# mk312lite_V3.net
KiCad netlist of a schematic drawn in EAGLE
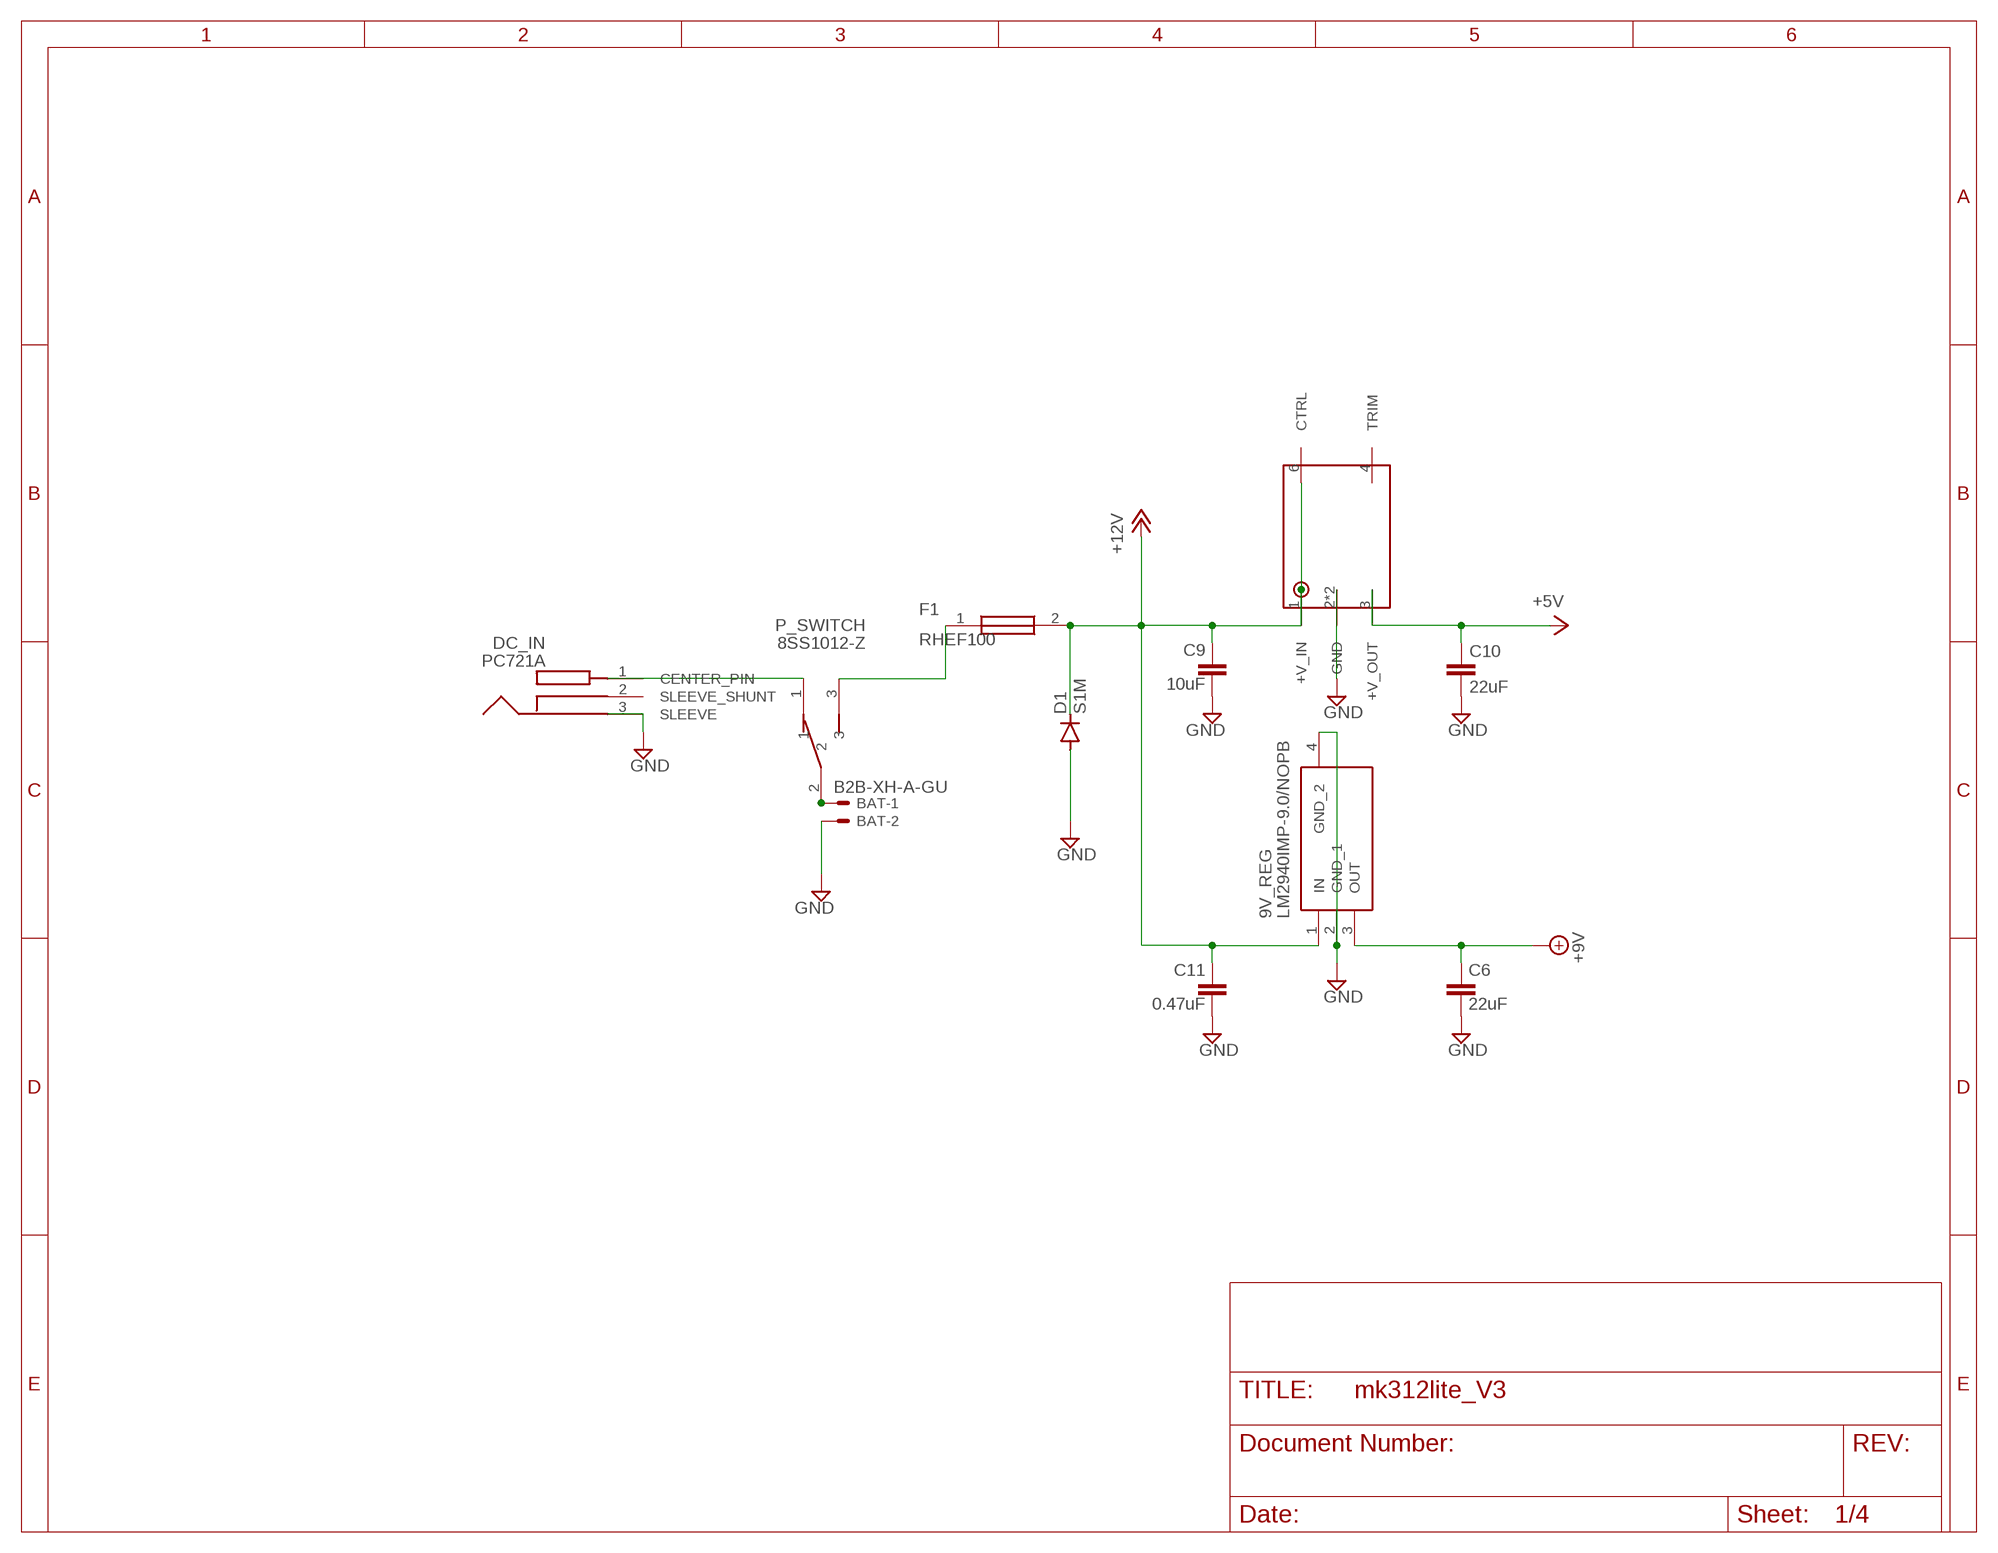
[diagram p0: schematic, sheet 1]
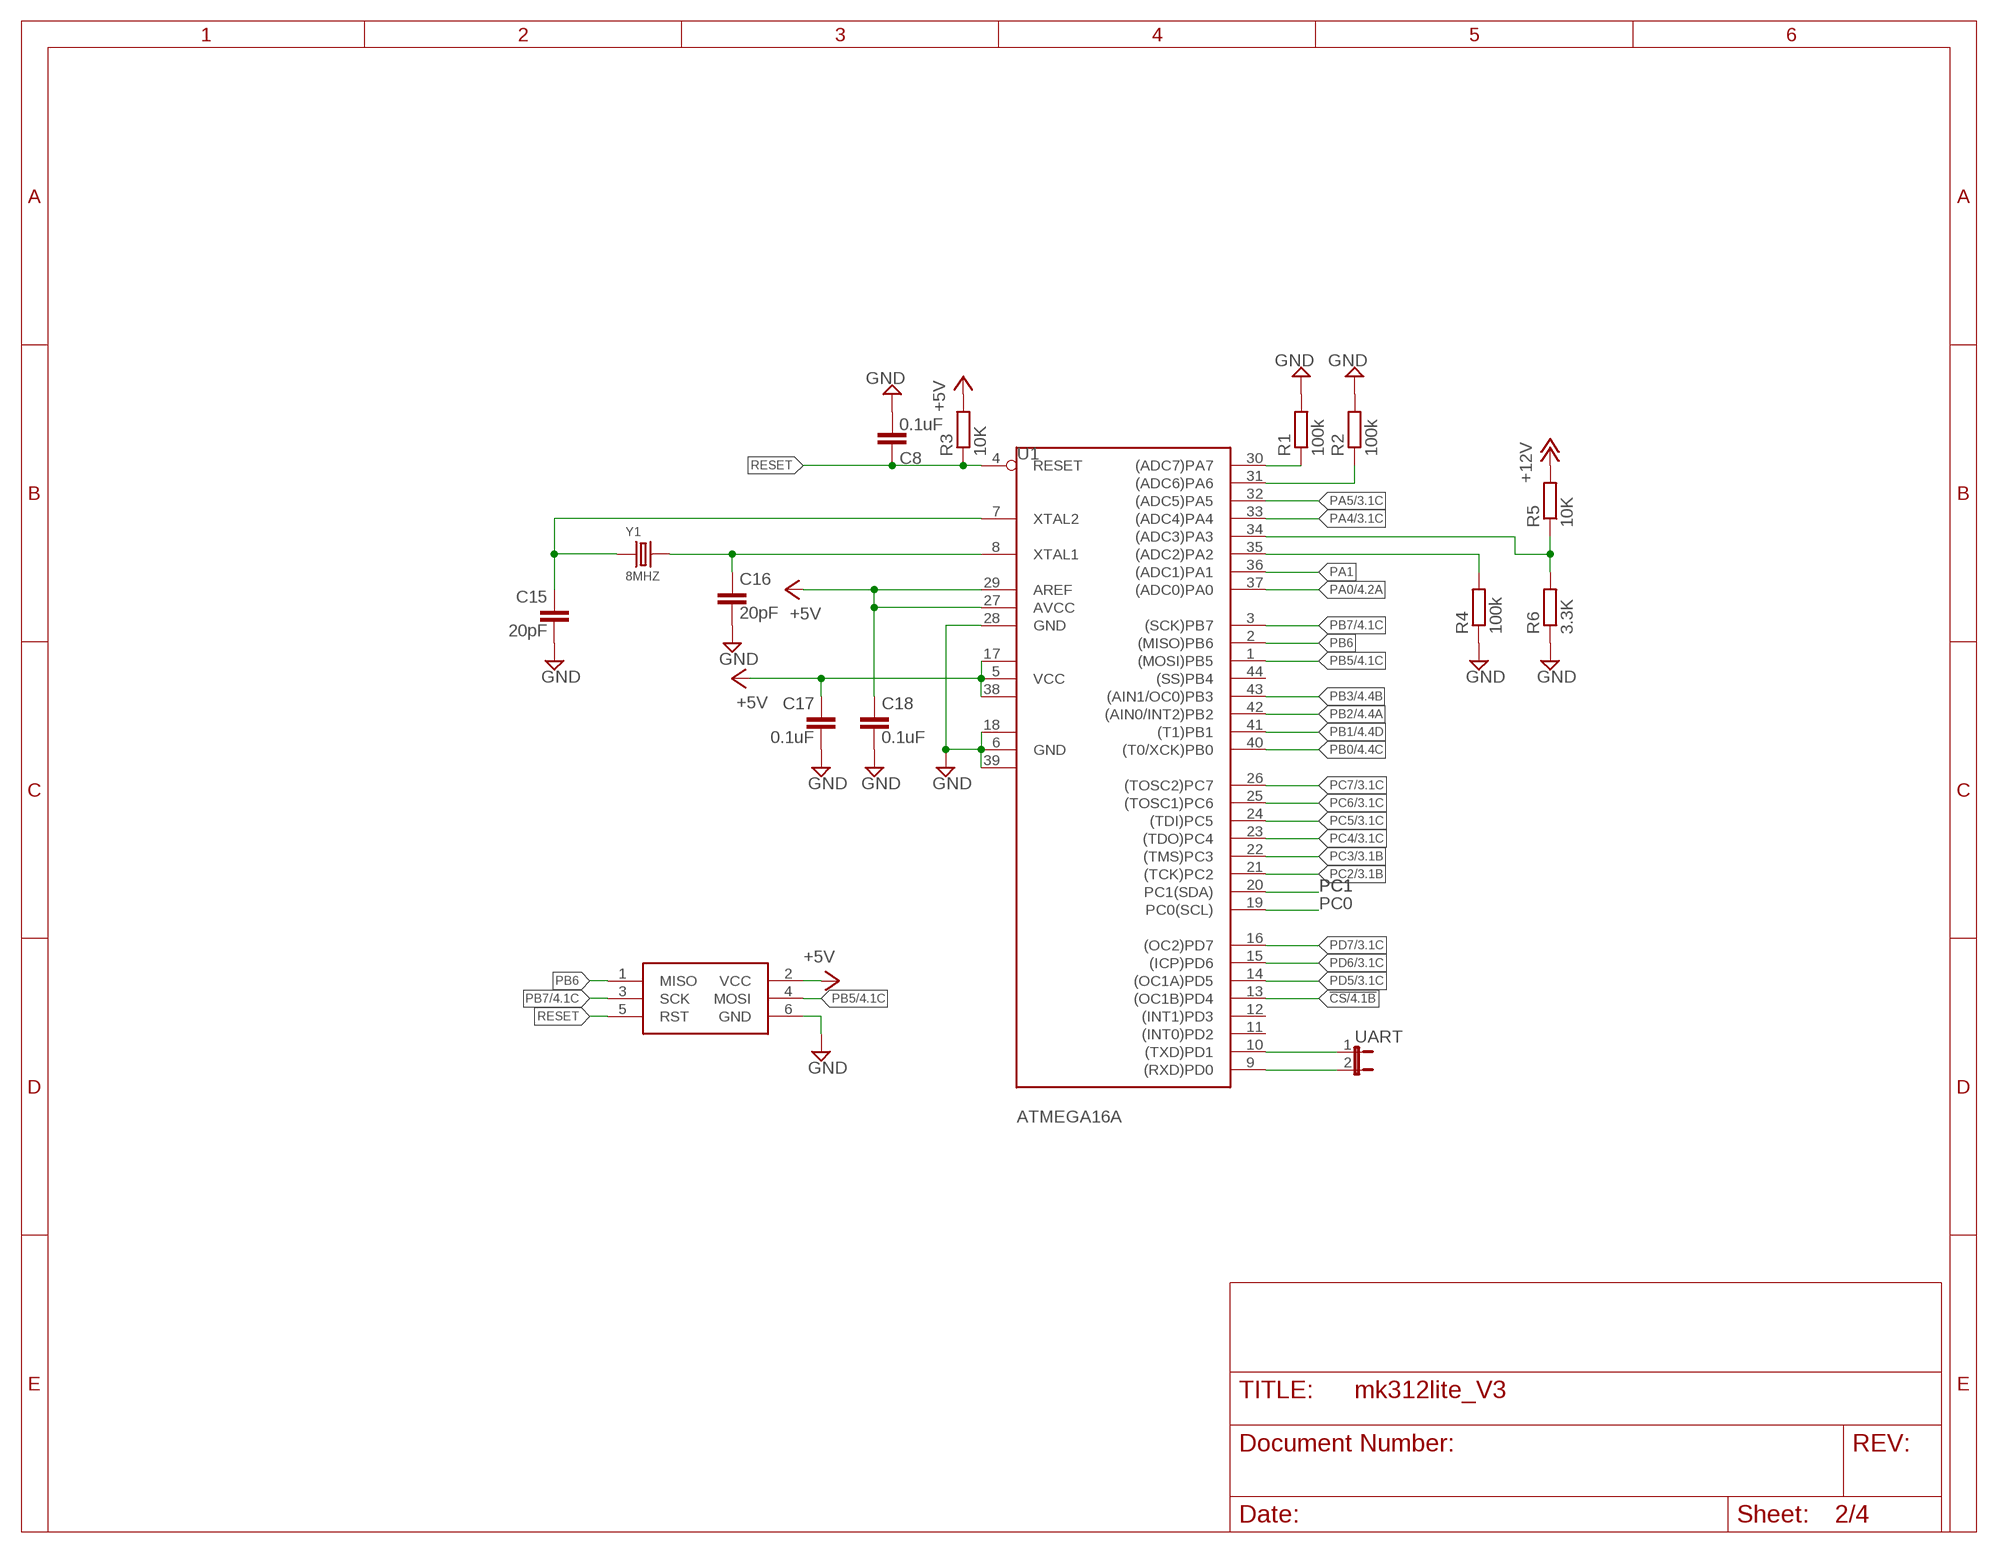
[diagram p1: schematic, sheet 2]
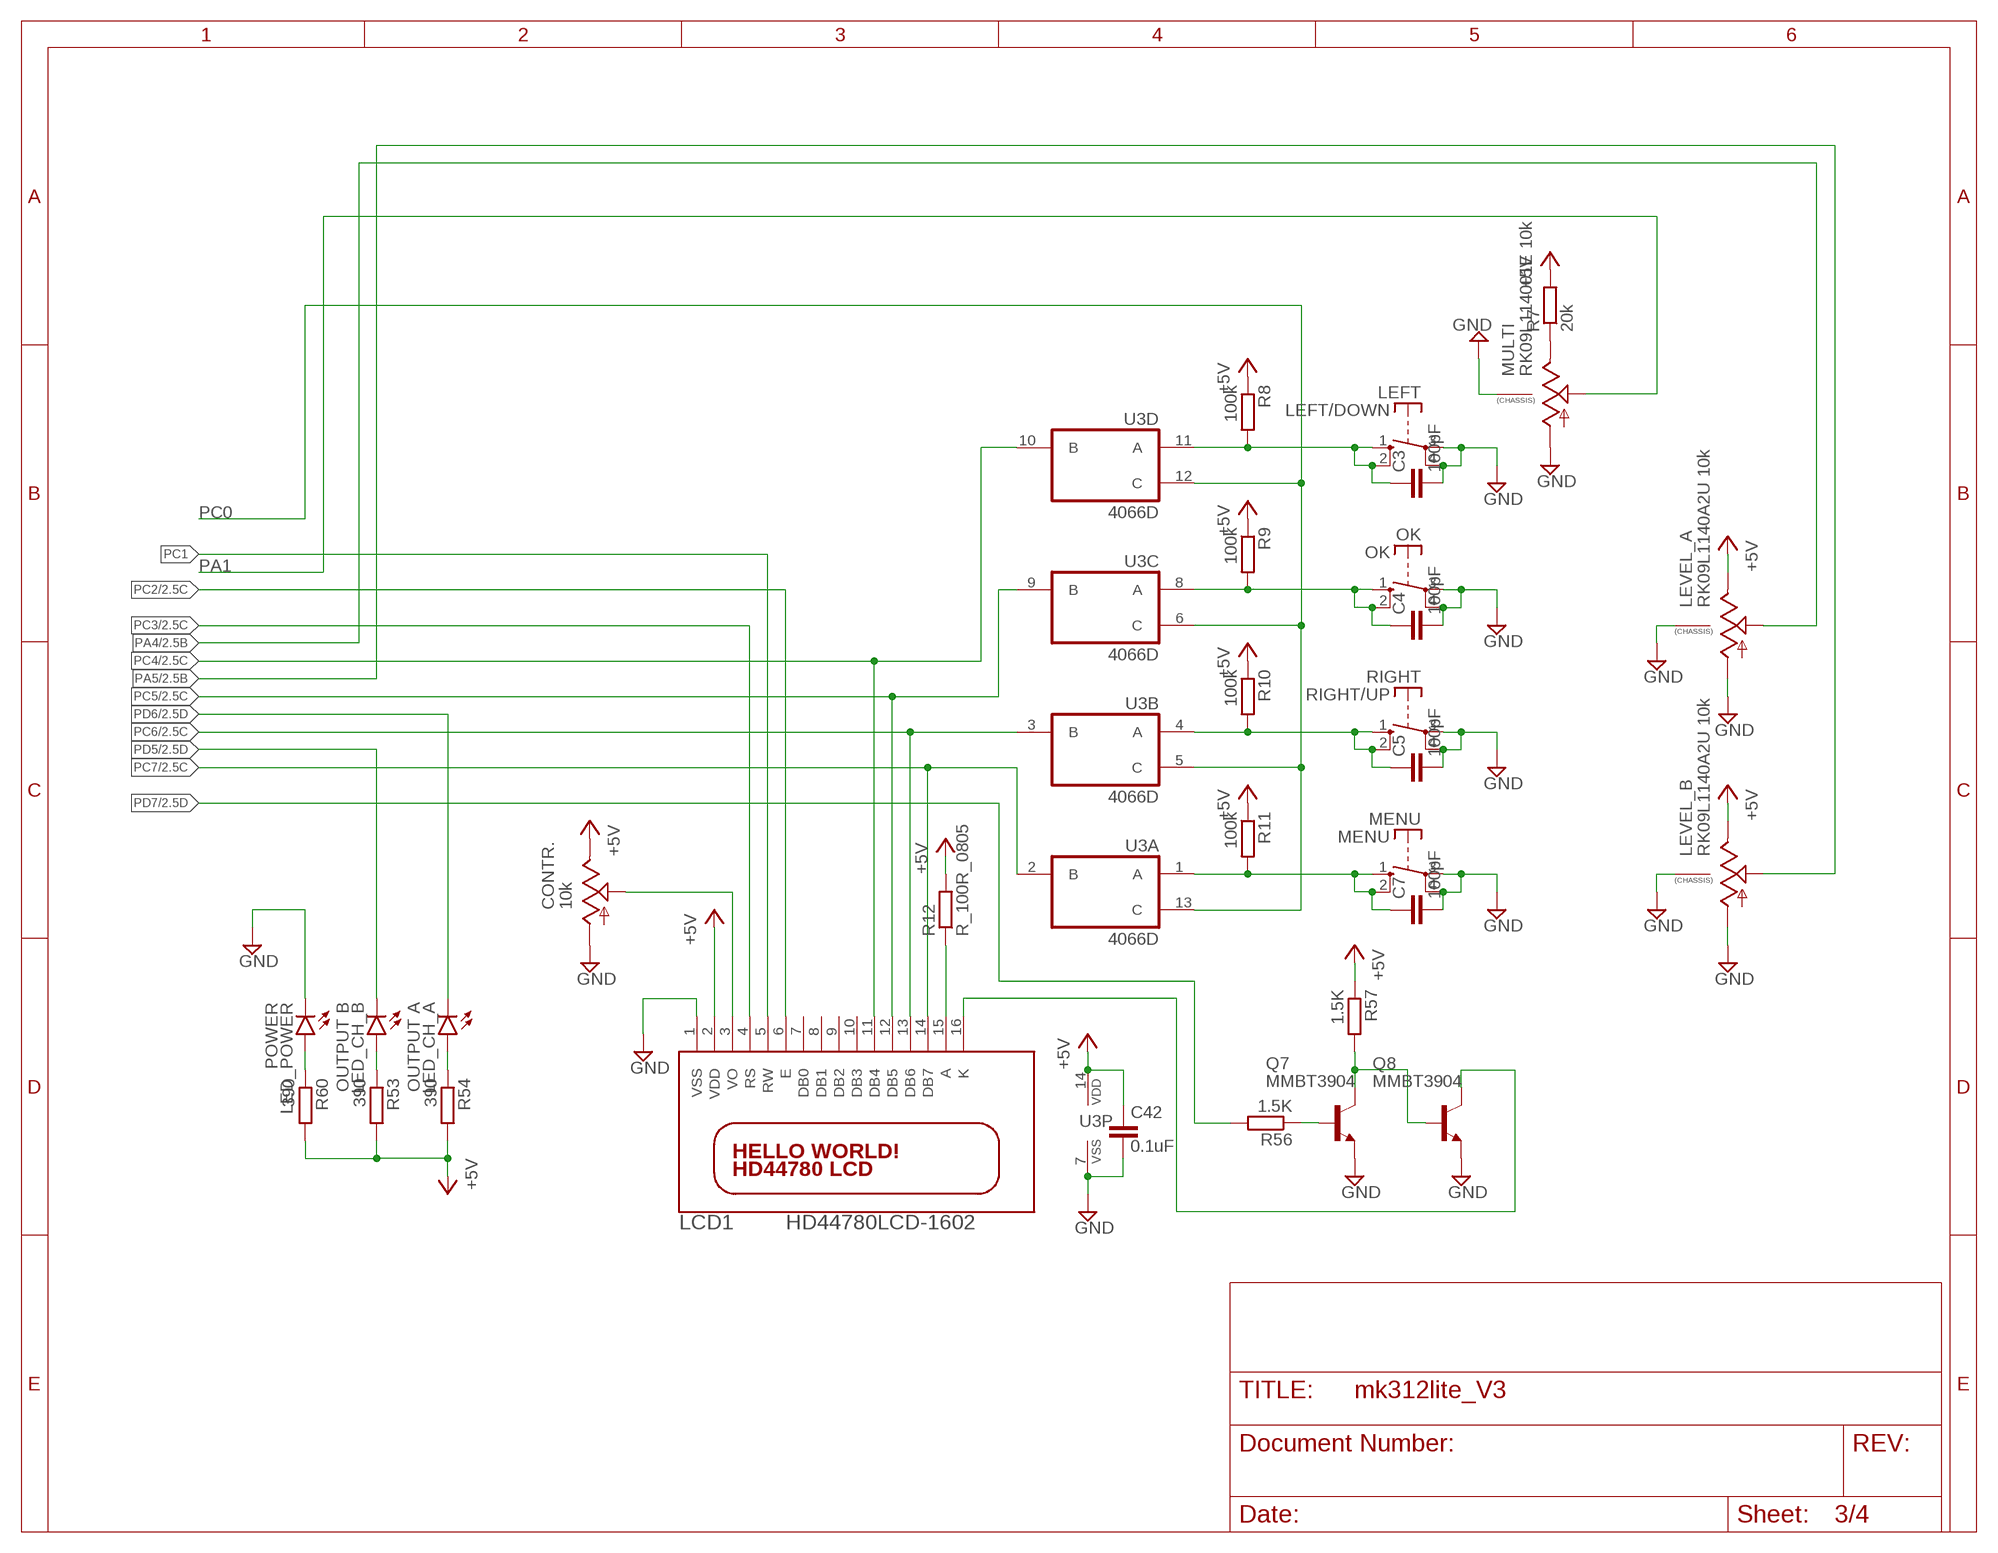
[diagram p2: schematic, sheet 3]
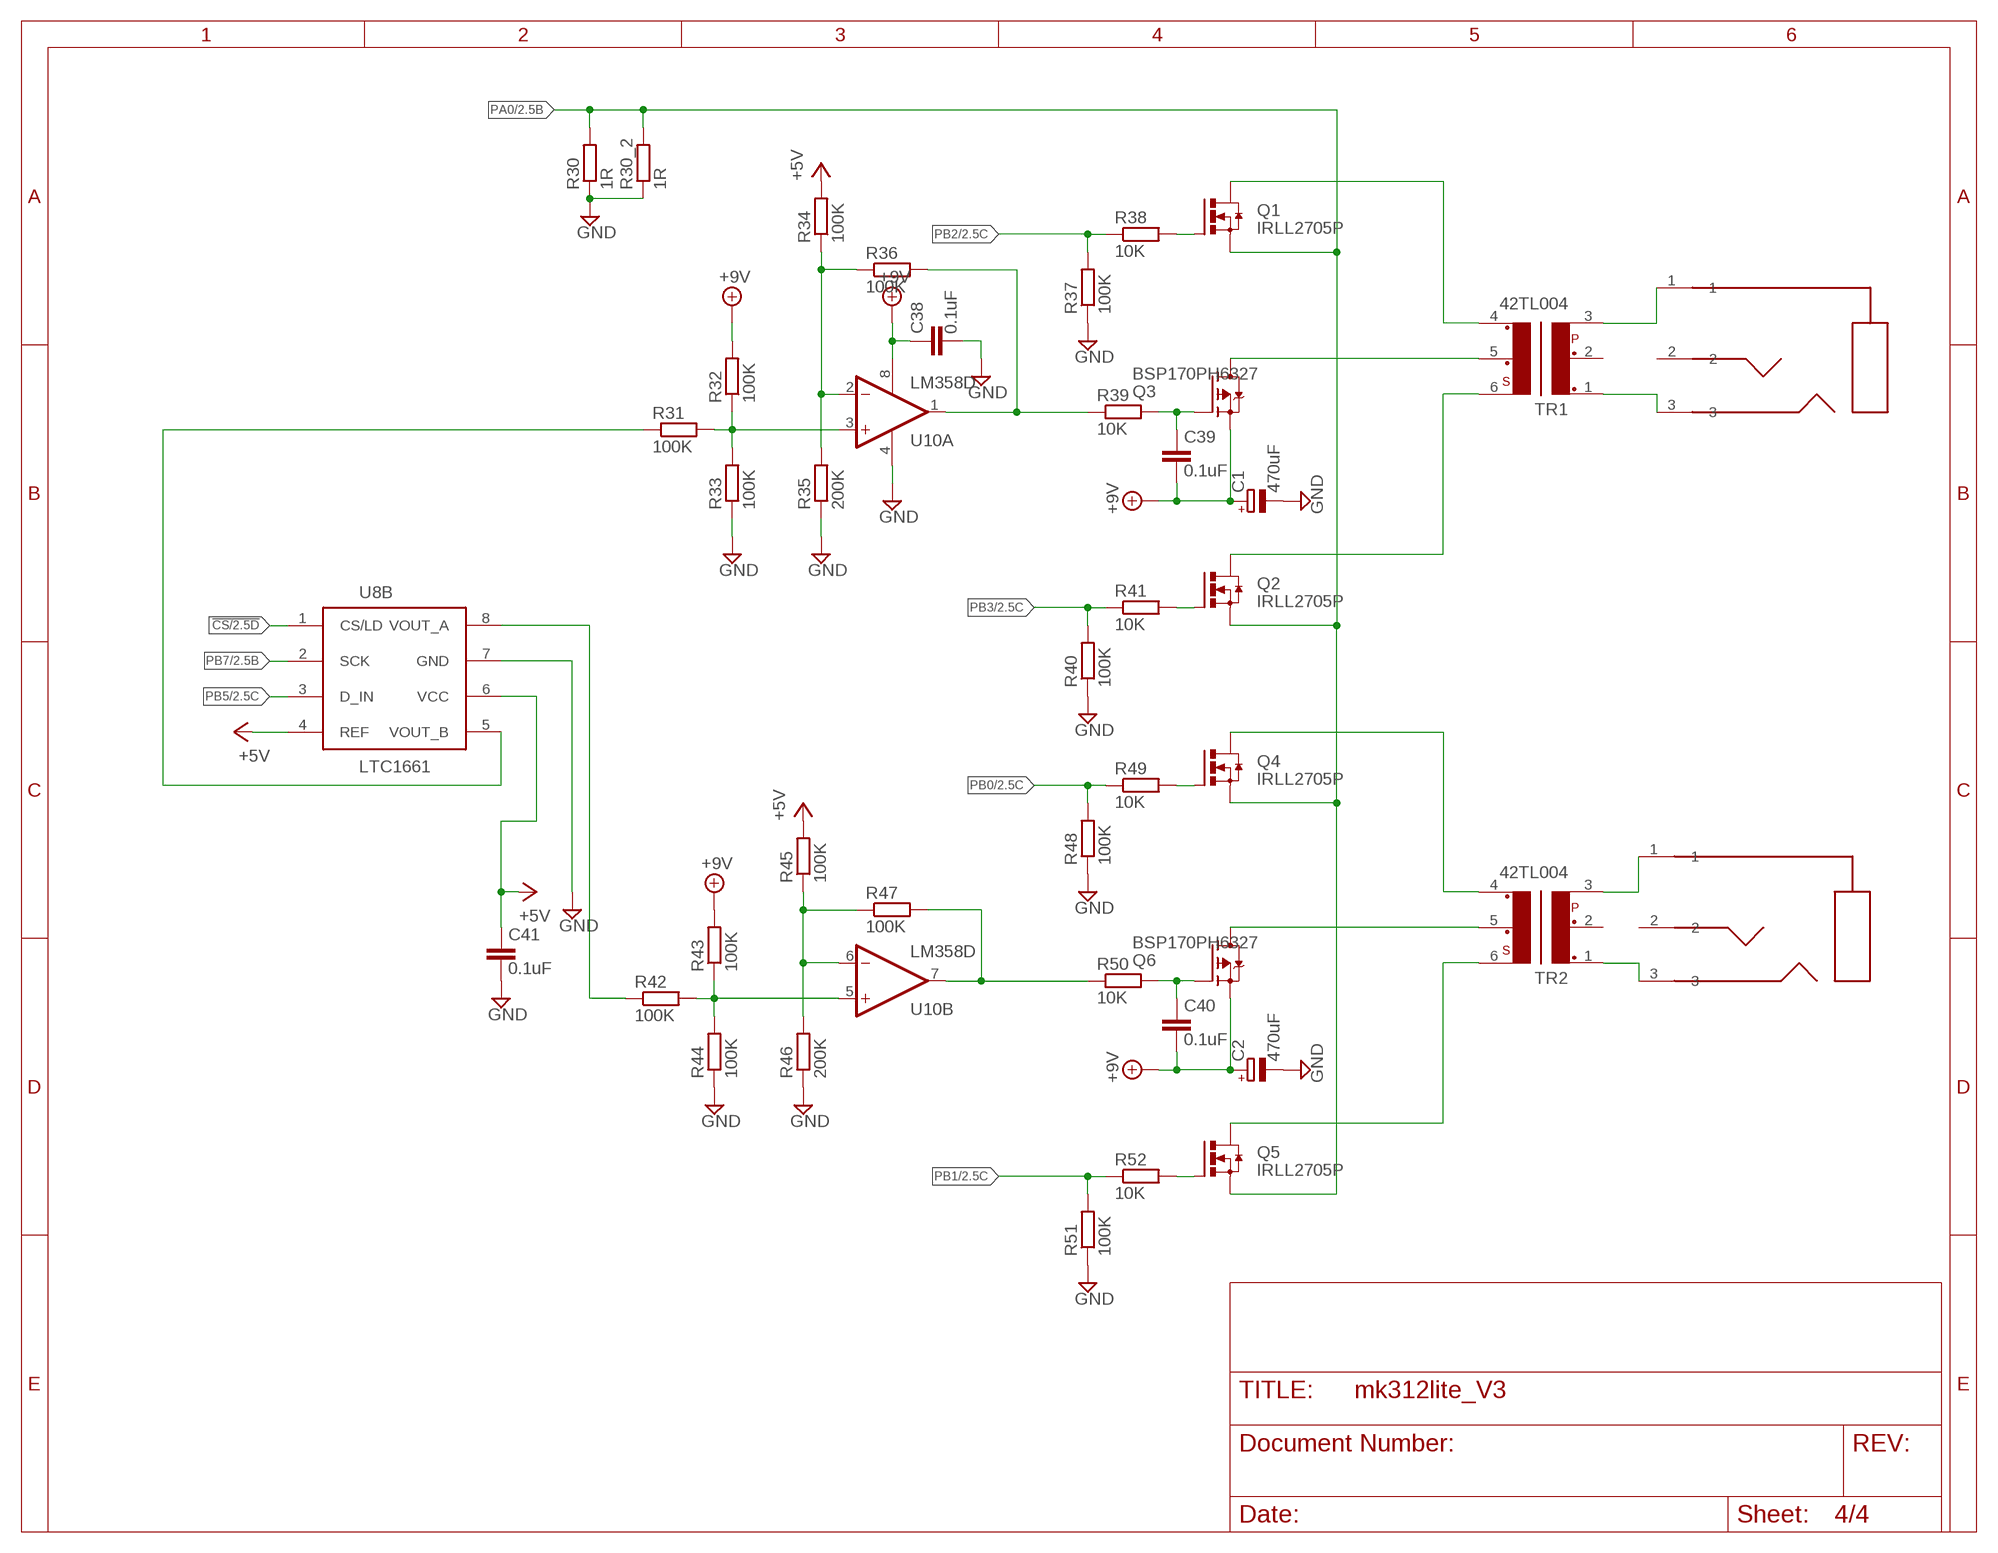
[diagram p3: schematic, sheet 4]

(export (version "E")
  (design (tool "Eeschema 10.0.6"))
  (components
    (comp (ref "9V_REG")
      (value "LM2940IMP-9.0/NOPB")
      (footprint "eagle-import:SOT230P700X180-4N")
      (fields (field (name "MOUSER_PART_NUMBER") "926-LM2940IMP90NOPB"))
      (libsource (lib "eagle-import") (part "LM2940IMP-9.0_NOPB"))
    )
    (comp (ref "BAT")
      (value "B2B-XH-A-GU")
      (footprint "eagle-import:JST-XH-02-PACKAGE-LONG-PAD")
      (libsource (lib "eagle-import") (part "JST-XH-02-PIN-LONG-PAD"))
    )
    (comp (ref "C6")
      (value "22uF")
      (footprint "eagle-import:C1206")
      (libsource (lib "eagle-import") (part "C-EUC1206"))
    )
    (comp (ref "C9")
      (value "10uF")
      (footprint "eagle-import:C0805")
      (libsource (lib "eagle-import") (part "C-EUC0805"))
    )
    (comp (ref "C10")
      (value "22uF")
      (footprint "eagle-import:C1206")
      (libsource (lib "eagle-import") (part "C-EUC1206"))
    )
    (comp (ref "C11")
      (value "0.47uF")
      (footprint "eagle-import:C0805")
      (libsource (lib "eagle-import") (part "C-EUC0805"))
    )
    (comp (ref "D1")
      (value "S1M")
      (footprint "eagle-import:SMA")
      (libsource (lib "eagle-import") (part "S1M"))
    )
    (comp (ref "DC_IN")
      (value "PC721A")
      (footprint "eagle-import:PC721A")
      (fields (field (name "MOUSER_PART_NUMBER") "502-PC721A"))
      (libsource (lib "eagle-import") (part "PC721A"))
    )
    (comp (ref "F1")
      (value "RHEF100")
      (footprint "eagle-import:RHEF1002")
      (fields
        (field (name "MANUFACTURER_PART_NUMBER") "RHEF100-2")
        (field (name "MOUSER_PART_NUMBER") "650-RHEF100-2")
      )
      (libsource (lib "eagle-import") (part "RHEF100-2"))
    )
    (comp (ref "P_SWITCH")
      (value "8SS1012-Z")
      (footprint "eagle-import:8SS1012Z")
      (libsource (lib "eagle-import") (part "8SS1012-Z"))
    )
    (comp (ref "U$1")
      (value "K7805MT-500R4")
      (footprint "eagle-import:DFN")
      (libsource (lib "eagle-import") (part "K7805MT-500R4"))
    )
    (comp (ref "C8")
      (value "0.1uF")
      (footprint "eagle-import:C0805")
      (libsource (lib "eagle-import") (part "C-EUC0805"))
    )
    (comp (ref "C15")
      (value "20pF")
      (footprint "eagle-import:C0603")
      (libsource (lib "eagle-import") (part "C-EUC0603"))
    )
    (comp (ref "C16")
      (value "20pF")
      (footprint "eagle-import:C0603")
      (libsource (lib "eagle-import") (part "C-EUC0603"))
    )
    (comp (ref "C17")
      (value "0.1uF")
      (footprint "eagle-import:C0805")
      (libsource (lib "eagle-import") (part "C-EUC0805"))
    )
    (comp (ref "C18")
      (value "0.1uF")
      (footprint "eagle-import:C0805")
      (libsource (lib "eagle-import") (part "C-EUC0805"))
    )
    (comp (ref "ISP1")
      (value "AVRISP-6")
      (footprint "eagle-import:AVRISP")
      (libsource (lib "eagle-import") (part "AVRISP-6"))
    )
    (comp (ref "R1")
      (value "100k")
      (footprint "eagle-import:R0805")
      (libsource (lib "eagle-import") (part "R-EU_R0805"))
    )
    (comp (ref "R2")
      (value "100k")
      (footprint "eagle-import:R0805")
      (libsource (lib "eagle-import") (part "R-EU_R0805"))
    )
    (comp (ref "R3")
      (value "10K")
      (footprint "eagle-import:R0805")
      (libsource (lib "eagle-import") (part "R-EU_R0805"))
    )
    (comp (ref "R4")
      (value "100k")
      (footprint "eagle-import:R0805")
      (libsource (lib "eagle-import") (part "R-EU_R0805"))
    )
    (comp (ref "R5")
      (value "10K")
      (footprint "eagle-import:R0805")
      (libsource (lib "eagle-import") (part "R-EU_R0805"))
    )
    (comp (ref "R6")
      (value "3.3K")
      (footprint "eagle-import:R0805")
      (libsource (lib "eagle-import") (part "R-EU_R0805"))
    )
    (comp (ref "U1")
      (value "ATMEGA16A")
      (footprint "eagle-import:TQFP44")
      (fields (field (name "MPN") "ATMEGA16-16AU"))
      (libsource (lib "eagle-import") (part "MEGA16-A"))
    )
    (comp (ref "UART")
      (value "JP1E")
      (footprint "eagle-import:JP1")
      (libsource (lib "eagle-import") (part "JP1E"))
    )
    (comp (ref "Y1")
      (value "8MHZ")
      (footprint "eagle-import:X2-SMD-5.0X3.2X1.3MM")
      (fields (field (name "MPN") "5032/2P"))
      (libsource (lib "eagle-import") (part "SMD-CRYSTAL-8MHZ-20PF-20PPM(2P-5.0X3.2MM)"))
    )
    (comp (ref "C3")
      (value "100pF")
      (footprint "eagle-import:C0805")
      (libsource (lib "eagle-import") (part "C-EUC0805"))
    )
    (comp (ref "C4")
      (value "100pF")
      (footprint "eagle-import:C0805")
      (libsource (lib "eagle-import") (part "C-EUC0805"))
    )
    (comp (ref "C5")
      (value "100pF")
      (footprint "eagle-import:C0805")
      (libsource (lib "eagle-import") (part "C-EUC0805"))
    )
    (comp (ref "C7")
      (value "100pF")
      (footprint "eagle-import:C0805")
      (libsource (lib "eagle-import") (part "C-EUC0805"))
    )
    (comp (ref "C42")
      (value "0.1uF")
      (footprint "eagle-import:C0805")
      (libsource (lib "eagle-import") (part "C-EUC0805"))
    )
    (comp (ref "CONTR.")
      (value "10k")
      (footprint "eagle-import:B25P")
      (libsource (lib "eagle-import") (part "TRIM_US-B25P"))
    )
    (comp (ref "LCD1")
      (value "HD44780LCD-1602")
      (footprint "eagle-import:LCD1602")
      (libsource (lib "eagle-import") (part "HD44780LCD-1602"))
    )
    (comp (ref "LED_CH_A")
      (value "OUTPUT A")
      (footprint "eagle-import:LED3MM")
      (libsource (lib "eagle-import") (part "LED3MM"))
    )
    (comp (ref "LED_CH_B")
      (value "OUTPUT B")
      (footprint "eagle-import:LED3MM")
      (libsource (lib "eagle-import") (part "LED3MM"))
    )
    (comp (ref "LED_POWER")
      (value "POWER")
      (footprint "eagle-import:LED3MM")
      (libsource (lib "eagle-import") (part "LED3MM"))
    )
    (comp (ref "LEFT")
      (value "LEFT/DOWN")
      (footprint "eagle-import:DTE6K")
      (libsource (lib "eagle-import") (part "DTE6K"))
    )
    (comp (ref "LEVEL_A")
      (value "RK09L1140A2U 10k")
      (footprint "eagle-import:9MM_SNAP-IN_POT")
      (libsource (lib "eagle-import") (part "9MM_SNAP-IN_POT_CHASSIS"))
    )
    (comp (ref "LEVEL_B")
      (value "RK09L1140A2U 10k")
      (footprint "eagle-import:9MM_SNAP-IN_POT")
      (libsource (lib "eagle-import") (part "9MM_SNAP-IN_POT_CHASSIS"))
    )
    (comp (ref "MENU")
      (value "MENU")
      (footprint "eagle-import:DTE6K")
      (libsource (lib "eagle-import") (part "DTE6K"))
    )
    (comp (ref "MULTI")
      (value "RK09L114001E 10k")
      (footprint "eagle-import:9MM_SNAP-IN_POT")
      (libsource (lib "eagle-import") (part "9MM_SNAP-IN_POT_CHASSIS"))
    )
    (comp (ref "OK")
      (value "OK")
      (footprint "eagle-import:DTE6K")
      (libsource (lib "eagle-import") (part "DTE6K"))
    )
    (comp (ref "Q7")
      (value "MMBT3904")
      (footprint "eagle-import:SOT23-BEC")
      (libsource (lib "eagle-import") (part "-NPN-SOT23-BECMMBT3904LT1"))
    )
    (comp (ref "Q8")
      (value "MMBT3904")
      (footprint "eagle-import:SOT23-BEC")
      (libsource (lib "eagle-import") (part "-NPN-SOT23-BECMMBT3904LT1"))
    )
    (comp (ref "R7")
      (value "20k")
      (footprint "eagle-import:R0805")
      (libsource (lib "eagle-import") (part "R-EU_R0805"))
    )
    (comp (ref "R8")
      (value "100k")
      (footprint "eagle-import:R0805")
      (libsource (lib "eagle-import") (part "R-EU_R0805"))
    )
    (comp (ref "R9")
      (value "100k")
      (footprint "eagle-import:R0805")
      (libsource (lib "eagle-import") (part "R-EU_R0805"))
    )
    (comp (ref "R10")
      (value "100k")
      (footprint "eagle-import:R0805")
      (libsource (lib "eagle-import") (part "R-EU_R0805"))
    )
    (comp (ref "R11")
      (value "100k")
      (footprint "eagle-import:R0805")
      (libsource (lib "eagle-import") (part "R-EU_R0805"))
    )
    (comp (ref "R12")
      (value "R_100R_0805")
      (footprint "eagle-import:R0805")
      (fields (field (name "LCSC_PART") "C17408"))
      (libsource (lib "eagle-import") (part "R__0805100R"))
    )
    (comp (ref "R53")
      (value "390")
      (footprint "eagle-import:R0805")
      (libsource (lib "eagle-import") (part "R-EU_R0805"))
    )
    (comp (ref "R54")
      (value "390")
      (footprint "eagle-import:R0805")
      (libsource (lib "eagle-import") (part "R-EU_R0805"))
    )
    (comp (ref "R56")
      (value "1.5K")
      (footprint "eagle-import:R0805")
      (libsource (lib "eagle-import") (part "R-EU_R0805"))
    )
    (comp (ref "R57")
      (value "1.5K")
      (footprint "eagle-import:R0805")
      (libsource (lib "eagle-import") (part "R-EU_R0805"))
    )
    (comp (ref "R60")
      (value "390")
      (footprint "eagle-import:R0805")
      (libsource (lib "eagle-import") (part "R-EU_R0805"))
    )
    (comp (ref "RIGHT")
      (value "RIGHT/UP")
      (footprint "eagle-import:DTE6K")
      (libsource (lib "eagle-import") (part "DTE6K"))
    )
    (comp (ref "U3")
      (value "4066D")
      (footprint "eagle-import:SO14")
      (libsource (lib "eagle-import") (part "4066D"))
    )
    (comp (ref "C1")
      (value "470uF")
      (footprint "eagle-import:150CLZ-1010")
      (libsource (lib "eagle-import") (part "CPOL-EU150CLZ-1010"))
    )
    (comp (ref "C2")
      (value "470uF")
      (footprint "eagle-import:150CLZ-1010")
      (libsource (lib "eagle-import") (part "CPOL-EU150CLZ-1010"))
    )
    (comp (ref "C38")
      (value "0.1uF")
      (footprint "eagle-import:C0805")
      (libsource (lib "eagle-import") (part "C-EUC0805"))
    )
    (comp (ref "C39")
      (value "0.1uF")
      (footprint "eagle-import:C0805")
      (libsource (lib "eagle-import") (part "C-EUC0805"))
    )
    (comp (ref "C40")
      (value "0.1uF")
      (footprint "eagle-import:C0805")
      (libsource (lib "eagle-import") (part "C-EUC0805"))
    )
    (comp (ref "C41")
      (value "0.1uF")
      (footprint "eagle-import:C0805")
      (libsource (lib "eagle-import") (part "C-EUC0805"))
    )
    (comp (ref "CHAN_A")
      (value "PJ-301C")
      (footprint "eagle-import:PJ-301C")
      (libsource (lib "eagle-import") (part "PC-301C"))
    )
    (comp (ref "CHAN_B")
      (value "PJ-301C")
      (footprint "eagle-import:PJ-301C")
      (libsource (lib "eagle-import") (part "PC-301C"))
    )
    (comp (ref "Q1")
      (value "IRLL2705P")
      (footprint "eagle-import:SOT223")
      (libsource (lib "eagle-import") (part "N-HEXFET-2D_?-SOT232IRLL2705"))
    )
    (comp (ref "Q2")
      (value "IRLL2705P")
      (footprint "eagle-import:SOT223")
      (libsource (lib "eagle-import") (part "N-HEXFET-2D_?-SOT232IRLL2705"))
    )
    (comp (ref "Q3")
      (value "BSP170PH6327")
      (footprint "eagle-import:SOT230P700X180-4N")
      (libsource (lib "eagle-import") (part "IRFL9014TRPBF"))
    )
    (comp (ref "Q4")
      (value "IRLL2705P")
      (footprint "eagle-import:SOT223")
      (libsource (lib "eagle-import") (part "N-HEXFET-2D_?-SOT232IRLL2705"))
    )
    (comp (ref "Q5")
      (value "IRLL2705P")
      (footprint "eagle-import:SOT223")
      (libsource (lib "eagle-import") (part "N-HEXFET-2D_?-SOT232IRLL2705"))
    )
    (comp (ref "Q6")
      (value "BSP170PH6327")
      (footprint "eagle-import:SOT230P700X180-4N")
      (libsource (lib "eagle-import") (part "IRFL9014TRPBF"))
    )
    (comp (ref "R30")
      (value "1R")
      (footprint "eagle-import:R1206")
      (libsource (lib "eagle-import") (part "R-EU_R1206"))
    )
    (comp (ref "R30_2")
      (value "1R")
      (footprint "eagle-import:R1206")
      (libsource (lib "eagle-import") (part "R-EU_R1206"))
    )
    (comp (ref "R31")
      (value "100K")
      (footprint "eagle-import:R0805")
      (libsource (lib "eagle-import") (part "R-EU_R0805"))
    )
    (comp (ref "R32")
      (value "100K")
      (footprint "eagle-import:R0805")
      (libsource (lib "eagle-import") (part "R-EU_R0805"))
    )
    (comp (ref "R33")
      (value "100K")
      (footprint "eagle-import:R0805")
      (libsource (lib "eagle-import") (part "R-EU_R0805"))
    )
    (comp (ref "R34")
      (value "100K")
      (footprint "eagle-import:R0805")
      (libsource (lib "eagle-import") (part "R-EU_R0805"))
    )
    (comp (ref "R35")
      (value "200K")
      (footprint "eagle-import:R0805")
      (libsource (lib "eagle-import") (part "R-EU_R0805"))
    )
    (comp (ref "R36")
      (value "100K")
      (footprint "eagle-import:R0805")
      (libsource (lib "eagle-import") (part "R-EU_R0805"))
    )
    (comp (ref "R37")
      (value "100K")
      (footprint "eagle-import:R0805")
      (libsource (lib "eagle-import") (part "R-EU_R0805"))
    )
    (comp (ref "R38")
      (value "10K")
      (footprint "eagle-import:R0805")
      (libsource (lib "eagle-import") (part "R-EU_R0805"))
    )
    (comp (ref "R39")
      (value "10K")
      (footprint "eagle-import:R0805")
      (libsource (lib "eagle-import") (part "R-EU_R0805"))
    )
    (comp (ref "R40")
      (value "100K")
      (footprint "eagle-import:R0805")
      (libsource (lib "eagle-import") (part "R-EU_R0805"))
    )
    (comp (ref "R41")
      (value "10K")
      (footprint "eagle-import:R0805")
      (libsource (lib "eagle-import") (part "R-EU_R0805"))
    )
    (comp (ref "R42")
      (value "100K")
      (footprint "eagle-import:R0805")
      (libsource (lib "eagle-import") (part "R-EU_R0805"))
    )
    (comp (ref "R43")
      (value "100K")
      (footprint "eagle-import:R0805")
      (libsource (lib "eagle-import") (part "R-EU_R0805"))
    )
    (comp (ref "R44")
      (value "100K")
      (footprint "eagle-import:R0805")
      (libsource (lib "eagle-import") (part "R-EU_R0805"))
    )
    (comp (ref "R45")
      (value "100K")
      (footprint "eagle-import:R0805")
      (libsource (lib "eagle-import") (part "R-EU_R0805"))
    )
    (comp (ref "R46")
      (value "200K")
      (footprint "eagle-import:R0805")
      (libsource (lib "eagle-import") (part "R-EU_R0805"))
    )
    (comp (ref "R47")
      (value "100K")
      (footprint "eagle-import:R0805")
      (libsource (lib "eagle-import") (part "R-EU_R0805"))
    )
    (comp (ref "R48")
      (value "100K")
      (footprint "eagle-import:R0805")
      (libsource (lib "eagle-import") (part "R-EU_R0805"))
    )
    (comp (ref "R49")
      (value "10K")
      (footprint "eagle-import:R0805")
      (libsource (lib "eagle-import") (part "R-EU_R0805"))
    )
    (comp (ref "R50")
      (value "10K")
      (footprint "eagle-import:R0805")
      (libsource (lib "eagle-import") (part "R-EU_R0805"))
    )
    (comp (ref "R51")
      (value "100K")
      (footprint "eagle-import:R0805")
      (libsource (lib "eagle-import") (part "R-EU_R0805"))
    )
    (comp (ref "R52")
      (value "10K")
      (footprint "eagle-import:R0805")
      (libsource (lib "eagle-import") (part "R-EU_R0805"))
    )
    (comp (ref "TR1")
      (value "42TL004")
      (footprint "eagle-import:42TL")
      (libsource (lib "eagle-import") (part "42T?L023"))
    )
    (comp (ref "TR2")
      (value "42TL004")
      (footprint "eagle-import:42TL")
      (libsource (lib "eagle-import") (part "42T?L023"))
    )
    (comp (ref "U8B")
      (value "LTC1661")
      (footprint "eagle-import:MSOP8")
      (libsource (lib "eagle-import") (part "LTC1661IMS8"))
    )
    (comp (ref "U10")
      (value "LM358D")
      (footprint "eagle-import:SO08")
      (libsource (lib "eagle-import") (part "LM358D"))
    )
  )
  (nets
    (net (code "1") (name "+5V") (class "Default")
      (node (ref "C10") (pin "1") (pinfunction "1_1") (pintype "passive"))
      (node (ref "C17") (pin "1") (pinfunction "1_1") (pintype "passive"))
      (node (ref "C18") (pin "1") (pinfunction "1_1") (pintype "passive"))
      (node (ref "C41") (pin "1") (pinfunction "1_1") (pintype "passive"))
      (node (ref "C42") (pin "1") (pinfunction "1_1") (pintype "passive"))
      (node (ref "CONTR.") (pin "E") (pinfunction "E_E") (pintype "passive"))
      (node (ref "ISP1") (pin "2") (pinfunction "VCC_2") (pintype "power_in"))
      (node (ref "LCD1") (pin "2") (pinfunction "VDD_2") (pintype "power_in"))
      (node (ref "LEVEL_A") (pin "3") (pinfunction "E_3") (pintype "passive"))
      (node (ref "LEVEL_B") (pin "3") (pinfunction "E_3") (pintype "passive"))
      (node (ref "R10") (pin "1") (pinfunction "1_1") (pintype "passive"))
      (node (ref "R11") (pin "1") (pinfunction "1_1") (pintype "passive"))
      (node (ref "R12") (pin "2") (pinfunction "2_2") (pintype "passive"))
      (node (ref "R3") (pin "2") (pinfunction "2_2") (pintype "passive"))
      (node (ref "R34") (pin "2") (pinfunction "2_2") (pintype "passive"))
      (node (ref "R45") (pin "2") (pinfunction "2_2") (pintype "passive"))
      (node (ref "R53") (pin "2") (pinfunction "2_2") (pintype "passive"))
      (node (ref "R54") (pin "2") (pinfunction "2_2") (pintype "passive"))
      (node (ref "R57") (pin "1") (pinfunction "1_1") (pintype "passive"))
      (node (ref "R60") (pin "2") (pinfunction "2_2") (pintype "passive"))
      (node (ref "R7") (pin "2") (pinfunction "2_2") (pintype "passive"))
      (node (ref "R8") (pin "1") (pinfunction "1_1") (pintype "passive"))
      (node (ref "R9") (pin "1") (pinfunction "1_1") (pintype "passive"))
      (node (ref "U$1") (pin "3") (pinfunction "+V_OUT_3") (pintype "output"))
      (node (ref "U1") (pin "17") (pinfunction "VCC1_17") (pintype "power_in"))
      (node (ref "U1") (pin "27") (pinfunction "AVCC_27") (pintype "power_in"))
      (node (ref "U1") (pin "29") (pinfunction "AREF_29") (pintype "passive"))
      (node (ref "U1") (pin "38") (pinfunction "VCC2_38") (pintype "power_in"))
      (node (ref "U1") (pin "5") (pinfunction "VCC_5") (pintype "power_in"))
      (node (ref "U3") (pin "14") (pinfunction "VDD_14") (pintype "power_in"))
      (node (ref "U8B") (pin "4") (pinfunction "REF_4") (pintype "input"))
      (node (ref "U8B") (pin "6") (pinfunction "VCC_6") (pintype "power_in"))
    )
    (net (code "2") (name "+9V") (class "Default")
      (node (ref "9V_REG") (pin "3") (pinfunction "OUT_3") (pintype "bidirectional"))
      (node (ref "C1") (pin "+") (pinfunction "+_+") (pintype "passive"))
      (node (ref "C2") (pin "+") (pinfunction "+_+") (pintype "passive"))
      (node (ref "C38") (pin "1") (pinfunction "1_1") (pintype "passive"))
      (node (ref "C39") (pin "2") (pinfunction "2_2") (pintype "passive"))
      (node (ref "C40") (pin "2") (pinfunction "2_2") (pintype "passive"))
      (node (ref "C6") (pin "1") (pinfunction "1_1") (pintype "passive"))
      (node (ref "Q3") (pin "3") (pinfunction "S_3") (pintype "passive"))
      (node (ref "Q6") (pin "3") (pinfunction "S_3") (pintype "passive"))
      (node (ref "R32") (pin "2") (pinfunction "2_2") (pintype "passive"))
      (node (ref "R43") (pin "2") (pinfunction "2_2") (pintype "passive"))
      (node (ref "U10") (pin "8") (pinfunction "V+_8") (pintype "power_in"))
    )
    (net (code "3") (name "+12V") (class "Default")
      (node (ref "9V_REG") (pin "1") (pinfunction "IN_1") (pintype "bidirectional"))
      (node (ref "C11") (pin "1") (pinfunction "1_1") (pintype "passive"))
      (node (ref "C9") (pin "1") (pinfunction "1_1") (pintype "passive"))
      (node (ref "D1") (pin "C") (pinfunction "C_C") (pintype "passive"))
      (node (ref "F1") (pin "2") (pinfunction "2_2") (pintype "bidirectional"))
      (node (ref "R5") (pin "2") (pinfunction "2_2") (pintype "passive"))
      (node (ref "U$1") (pin "1") (pinfunction "+V_IN_1") (pintype "input"))
      (node (ref "U$1") (pin "6") (pinfunction "CTRL_6") (pintype "input"))
    )
    (net (code "4") (name "GND") (class "Default")
      (node (ref "9V_REG") (pin "2") (pinfunction "GND_1_2") (pintype "bidirectional"))
      (node (ref "9V_REG") (pin "4") (pinfunction "GND_2_4") (pintype "bidirectional"))
      (node (ref "BAT") (pin "2") (pinfunction "S_2") (pintype "passive"))
      (node (ref "C1") (pin "-") (pinfunction "-_-") (pintype "passive"))
      (node (ref "C10") (pin "2") (pinfunction "2_2") (pintype "passive"))
      (node (ref "C11") (pin "2") (pinfunction "2_2") (pintype "passive"))
      (node (ref "C15") (pin "2") (pinfunction "2_2") (pintype "passive"))
      (node (ref "C16") (pin "2") (pinfunction "2_2") (pintype "passive"))
      (node (ref "C17") (pin "2") (pinfunction "2_2") (pintype "passive"))
      (node (ref "C18") (pin "2") (pinfunction "2_2") (pintype "passive"))
      (node (ref "C2") (pin "-") (pinfunction "-_-") (pintype "passive"))
      (node (ref "C3") (pin "2") (pinfunction "2_2") (pintype "passive"))
      (node (ref "C38") (pin "2") (pinfunction "2_2") (pintype "passive"))
      (node (ref "C4") (pin "2") (pinfunction "2_2") (pintype "passive"))
      (node (ref "C41") (pin "2") (pinfunction "2_2") (pintype "passive"))
      (node (ref "C42") (pin "2") (pinfunction "2_2") (pintype "passive"))
      (node (ref "C5") (pin "2") (pinfunction "2_2") (pintype "passive"))
      (node (ref "C6") (pin "2") (pinfunction "2_2") (pintype "passive"))
      (node (ref "C7") (pin "2") (pinfunction "2_2") (pintype "passive"))
      (node (ref "C8") (pin "2") (pinfunction "2_2") (pintype "passive"))
      (node (ref "C9") (pin "2") (pinfunction "2_2") (pintype "passive"))
      (node (ref "CONTR.") (pin "A") (pinfunction "A_A") (pintype "passive"))
      (node (ref "D1") (pin "A") (pinfunction "A_A") (pintype "passive"))
      (node (ref "DC_IN") (pin "3") (pinfunction "SLEEVE_3") (pintype "bidirectional"))
      (node (ref "ISP1") (pin "6") (pinfunction "GND_6") (pintype "power_in"))
      (node (ref "LCD1") (pin "1") (pinfunction "VSS_1") (pintype "power_in"))
      (node (ref "LED_POWER") (pin "K") (pinfunction "C_K") (pintype "passive"))
      (node (ref "LEFT") (pin "3") (pinfunction "P_3") (pintype "passive"))
      (node (ref "LEFT") (pin "4") (pinfunction "P_4") (pintype "passive"))
      (node (ref "LEVEL_A") (pin "1") (pinfunction "A_1") (pintype "passive"))
      (node (ref "LEVEL_A") (pin "CHASSIS2") (pinfunction "P$1_CHASSIS2") (pintype "passive"))
      (node (ref "LEVEL_B") (pin "1") (pinfunction "A_1") (pintype "passive"))
      (node (ref "LEVEL_B") (pin "CHASSIS2") (pinfunction "P$1_CHASSIS2") (pintype "passive"))
      (node (ref "MENU") (pin "3") (pinfunction "P_3") (pintype "passive"))
      (node (ref "MENU") (pin "4") (pinfunction "P_4") (pintype "passive"))
      (node (ref "MULTI") (pin "1") (pinfunction "A_1") (pintype "passive"))
      (node (ref "MULTI") (pin "CHASSIS2") (pinfunction "P$1_CHASSIS2") (pintype "passive"))
      (node (ref "OK") (pin "3") (pinfunction "P_3") (pintype "passive"))
      (node (ref "OK") (pin "4") (pinfunction "P_4") (pintype "passive"))
      (node (ref "Q7") (pin "E") (pinfunction "E_E") (pintype "passive"))
      (node (ref "Q8") (pin "E") (pinfunction "E_E") (pintype "passive"))
      (node (ref "R1") (pin "2") (pinfunction "2_2") (pintype "passive"))
      (node (ref "R2") (pin "2") (pinfunction "2_2") (pintype "passive"))
      (node (ref "R30") (pin "1") (pinfunction "1_1") (pintype "passive"))
      (node (ref "R30_2") (pin "1") (pinfunction "1_1") (pintype "passive"))
      (node (ref "R33") (pin "1") (pinfunction "1_1") (pintype "passive"))
      (node (ref "R35") (pin "1") (pinfunction "1_1") (pintype "passive"))
      (node (ref "R37") (pin "1") (pinfunction "1_1") (pintype "passive"))
      (node (ref "R4") (pin "1") (pinfunction "1_1") (pintype "passive"))
      (node (ref "R40") (pin "1") (pinfunction "1_1") (pintype "passive"))
      (node (ref "R44") (pin "1") (pinfunction "1_1") (pintype "passive"))
      (node (ref "R46") (pin "1") (pinfunction "1_1") (pintype "passive"))
      (node (ref "R48") (pin "1") (pinfunction "1_1") (pintype "passive"))
      (node (ref "R51") (pin "1") (pinfunction "1_1") (pintype "passive"))
      (node (ref "R6") (pin "1") (pinfunction "1_1") (pintype "passive"))
      (node (ref "RIGHT") (pin "3") (pinfunction "P_3") (pintype "passive"))
      (node (ref "RIGHT") (pin "4") (pinfunction "P_4") (pintype "passive"))
      (node (ref "U$1") (pin "2") (pinfunction "GND_2") (pintype "bidirectional"))
      (node (ref "U$1") (pin "5") (pinfunction "GND_5") (pintype "bidirectional"))
      (node (ref "U1") (pin "18") (pinfunction "GND1_18") (pintype "power_in"))
      (node (ref "U1") (pin "28") (pinfunction "GND_28") (pintype "power_in"))
      (node (ref "U1") (pin "39") (pinfunction "GND2_39") (pintype "power_in"))
      (node (ref "U1") (pin "6") (pinfunction "GND_6") (pintype "power_in"))
      (node (ref "U10") (pin "4") (pinfunction "V-_4") (pintype "power_in"))
      (node (ref "U3") (pin "7") (pinfunction "VSS_7") (pintype "power_in"))
      (node (ref "U8B") (pin "7") (pinfunction "GND_7") (pintype "power_in"))
    )
    (net (code "5") (name "Net-(BATA-S)") (class "Default")
      (node (ref "BAT") (pin "1") (pinfunction "S_1") (pintype "passive"))
      (node (ref "P_SWITCH") (pin "2") (pinfunction "2_2") (pintype "bidirectional"))
    )
    (net (code "6") (name "Net-(CHAN_A-Pad1)") (class "Default")
      (node (ref "CHAN_A") (pin "1") (pinfunction "1_1") (pintype "bidirectional"))
      (node (ref "TR1") (pin "3") (pinfunction "3_3") (pintype "passive"))
    )
    (net (code "7") (name "Net-(CHAN_A-Pad3)") (class "Default")
      (node (ref "CHAN_A") (pin "3") (pinfunction "3_3") (pintype "bidirectional"))
      (node (ref "TR1") (pin "1") (pinfunction "1_1") (pintype "passive"))
    )
    (net (code "8") (name "Net-(CHAN_B-Pad1)") (class "Default")
      (node (ref "CHAN_B") (pin "1") (pinfunction "1_1") (pintype "bidirectional"))
      (node (ref "TR2") (pin "3") (pinfunction "3_3") (pintype "passive"))
    )
    (net (code "9") (name "Net-(CHAN_B-Pad3)") (class "Default")
      (node (ref "CHAN_B") (pin "3") (pinfunction "3_3") (pintype "bidirectional"))
      (node (ref "TR2") (pin "1") (pinfunction "1_1") (pintype "passive"))
    )
    (net (code "10") (name "Net-(DC_IN-CENTER_PIN)") (class "Default")
      (node (ref "DC_IN") (pin "1") (pinfunction "CENTER_PIN_1") (pintype "bidirectional"))
      (node (ref "P_SWITCH") (pin "1") (pinfunction "1_1") (pintype "bidirectional"))
    )
    (net (code "11") (name "Net-(F1-Pad1)") (class "Default")
      (node (ref "F1") (pin "1") (pinfunction "1_1") (pintype "bidirectional"))
      (node (ref "P_SWITCH") (pin "3") (pinfunction "3_3") (pintype "bidirectional"))
    )
    (net (code "12") (name "Net-(LCD1-A)") (class "Default")
      (node (ref "LCD1") (pin "15") (pinfunction "A_15") (pintype "input"))
      (node (ref "R12") (pin "1") (pinfunction "1_1") (pintype "passive"))
    )
    (net (code "13") (name "Net-(LCD1-K)") (class "Default")
      (node (ref "LCD1") (pin "16") (pinfunction "K_16") (pintype "input"))
      (node (ref "Q8") (pin "C") (pinfunction "C_C") (pintype "passive"))
    )
    (net (code "14") (name "Net-(LCD1-VO)") (class "Default")
      (node (ref "CONTR.") (pin "S") (pinfunction "S_S") (pintype "passive"))
      (node (ref "LCD1") (pin "3") (pinfunction "VO_3") (pintype "input"))
    )
    (net (code "15") (name "Net-(LED_CH_A-PadA)") (class "Default")
      (node (ref "LED_CH_A") (pin "A") (pinfunction "A_A") (pintype "passive"))
      (node (ref "R54") (pin "1") (pinfunction "1_1") (pintype "passive"))
    )
    (net (code "16") (name "Net-(LED_CH_B-PadA)") (class "Default")
      (node (ref "LED_CH_B") (pin "A") (pinfunction "A_A") (pintype "passive"))
      (node (ref "R53") (pin "1") (pinfunction "1_1") (pintype "passive"))
    )
    (net (code "17") (name "Net-(LED_POWER-PadA)") (class "Default")
      (node (ref "LED_POWER") (pin "A") (pinfunction "A_A") (pintype "passive"))
      (node (ref "R60") (pin "1") (pinfunction "1_1") (pintype "passive"))
    )
    (net (code "18") (name "Net-(MULTI-E)") (class "Default")
      (node (ref "MULTI") (pin "3") (pinfunction "E_3") (pintype "passive"))
      (node (ref "R7") (pin "1") (pinfunction "1_1") (pintype "passive"))
    )
    (net (code "19") (name "Net-(Q1-D-Pad2)") (class "Default")
      (node (ref "Q1") (pin "2") (pinfunction "D_2") (pintype "passive"))
      (node (ref "Q1") (pin "4") (pinfunction "D_4") (pintype "passive"))
      (node (ref "TR1") (pin "4") (pinfunction "4_4") (pintype "passive"))
    )
    (net (code "20") (name "Net-(Q1-G)") (class "Default")
      (node (ref "Q1") (pin "1") (pinfunction "G_1") (pintype "passive"))
      (node (ref "R38") (pin "2") (pinfunction "2_2") (pintype "passive"))
    )
    (net (code "21") (name "Net-(Q2-D-Pad2)") (class "Default")
      (node (ref "Q2") (pin "2") (pinfunction "D_2") (pintype "passive"))
      (node (ref "Q2") (pin "4") (pinfunction "D_4") (pintype "passive"))
      (node (ref "TR1") (pin "6") (pinfunction "6_6") (pintype "passive"))
    )
    (net (code "22") (name "Net-(Q2-G)") (class "Default")
      (node (ref "Q2") (pin "1") (pinfunction "G_1") (pintype "passive"))
      (node (ref "R41") (pin "2") (pinfunction "2_2") (pintype "passive"))
    )
    (net (code "23") (name "Net-(Q3-D-Pad2)") (class "Default")
      (node (ref "Q3") (pin "2") (pinfunction "D_2") (pintype "passive"))
      (node (ref "Q3") (pin "4") (pinfunction "D_4") (pintype "passive"))
      (node (ref "TR1") (pin "5") (pinfunction "5_5") (pintype "passive"))
    )
    (net (code "24") (name "Net-(Q3-G)") (class "Default")
      (node (ref "C39") (pin "1") (pinfunction "1_1") (pintype "passive"))
      (node (ref "Q3") (pin "1") (pinfunction "G_1") (pintype "passive"))
      (node (ref "R39") (pin "2") (pinfunction "2_2") (pintype "passive"))
    )
    (net (code "25") (name "Net-(Q4-D-Pad2)") (class "Default")
      (node (ref "Q4") (pin "2") (pinfunction "D_2") (pintype "passive"))
      (node (ref "Q4") (pin "4") (pinfunction "D_4") (pintype "passive"))
      (node (ref "TR2") (pin "4") (pinfunction "4_4") (pintype "passive"))
    )
    (net (code "26") (name "Net-(Q4-G)") (class "Default")
      (node (ref "Q4") (pin "1") (pinfunction "G_1") (pintype "passive"))
      (node (ref "R49") (pin "2") (pinfunction "2_2") (pintype "passive"))
    )
    (net (code "27") (name "Net-(Q5-D-Pad2)") (class "Default")
      (node (ref "Q5") (pin "2") (pinfunction "D_2") (pintype "passive"))
      (node (ref "Q5") (pin "4") (pinfunction "D_4") (pintype "passive"))
      (node (ref "TR2") (pin "6") (pinfunction "6_6") (pintype "passive"))
    )
    (net (code "28") (name "Net-(Q5-G)") (class "Default")
      (node (ref "Q5") (pin "1") (pinfunction "G_1") (pintype "passive"))
      (node (ref "R52") (pin "2") (pinfunction "2_2") (pintype "passive"))
    )
    (net (code "29") (name "Net-(Q6-D-Pad2)") (class "Default")
      (node (ref "Q6") (pin "2") (pinfunction "D_2") (pintype "passive"))
      (node (ref "Q6") (pin "4") (pinfunction "D_4") (pintype "passive"))
      (node (ref "TR2") (pin "5") (pinfunction "5_5") (pintype "passive"))
    )
    (net (code "30") (name "Net-(Q6-G)") (class "Default")
      (node (ref "C40") (pin "1") (pinfunction "1_1") (pintype "passive"))
      (node (ref "Q6") (pin "1") (pinfunction "G_1") (pintype "passive"))
      (node (ref "R50") (pin "2") (pinfunction "2_2") (pintype "passive"))
    )
    (net (code "31") (name "Net-(Q7-PadB)") (class "Default")
      (node (ref "Q7") (pin "B") (pinfunction "B_B") (pintype "passive"))
      (node (ref "R56") (pin "1") (pinfunction "1_1") (pintype "passive"))
    )
    (net (code "32") (name "Net-(Q7-PadC)") (class "Default")
      (node (ref "Q7") (pin "C") (pinfunction "C_C") (pintype "passive"))
      (node (ref "Q8") (pin "B") (pinfunction "B_B") (pintype "passive"))
      (node (ref "R57") (pin "2") (pinfunction "2_2") (pintype "passive"))
    )
    (net (code "33") (name "Net-(U1-(ADC2)PA2)") (class "Default")
      (node (ref "R4") (pin "2") (pinfunction "2_2") (pintype "passive"))
      (node (ref "U1") (pin "35") (pinfunction "(ADC2)PA2_35") (pintype "bidirectional"))
    )
    (net (code "34") (name "Net-(U1-(ADC3)PA3)") (class "Default")
      (node (ref "R5") (pin "1") (pinfunction "1_1") (pintype "passive"))
      (node (ref "R6") (pin "2") (pinfunction "2_2") (pintype "passive"))
      (node (ref "U1") (pin "34") (pinfunction "(ADC3)PA3_34") (pintype "bidirectional"))
    )
    (net (code "35") (name "Net-(U1-(ADC6)PA6)") (class "Default")
      (node (ref "R2") (pin "1") (pinfunction "1_1") (pintype "passive"))
      (node (ref "U1") (pin "31") (pinfunction "(ADC6)PA6_31") (pintype "bidirectional"))
    )
    (net (code "36") (name "Net-(U1-(ADC7)PA7)") (class "Default")
      (node (ref "R1") (pin "1") (pinfunction "1_1") (pintype "passive"))
      (node (ref "U1") (pin "30") (pinfunction "(ADC7)PA7_30") (pintype "bidirectional"))
    )
    (net (code "37") (name "Net-(U1-(RXD)PD0)") (class "Default")
      (node (ref "U1") (pin "9") (pinfunction "(RXD)PD0_9") (pintype "bidirectional"))
      (node (ref "UART") (pin "2") (pinfunction "2_2") (pintype "passive"))
    )
    (net (code "38") (name "Net-(U1-(TXD)PD1)") (class "Default")
      (node (ref "U1") (pin "10") (pinfunction "(TXD)PD1_10") (pintype "bidirectional"))
      (node (ref "UART") (pin "1") (pinfunction "1_1") (pintype "passive"))
    )
    (net (code "39") (name "Net-(U1-XTAL1)") (class "Default")
      (node (ref "C16") (pin "1") (pinfunction "1_1") (pintype "passive"))
      (node (ref "U1") (pin "8") (pinfunction "XTAL1_8") (pintype "bidirectional"))
      (node (ref "Y1") (pin "2") (pinfunction "2_2") (pintype "passive"))
    )
    (net (code "40") (name "Net-(U1-XTAL2)") (class "Default")
      (node (ref "C15") (pin "1") (pinfunction "1_1") (pintype "passive"))
      (node (ref "U1") (pin "7") (pinfunction "XTAL2_7") (pintype "bidirectional"))
      (node (ref "Y1") (pin "1") (pinfunction "1_1") (pintype "passive"))
    )
    (net (code "41") (name "Net-(U3A-A)") (class "Default")
      (node (ref "C7") (pin "1") (pinfunction "1_1") (pintype "passive"))
      (node (ref "MENU") (pin "1") (pinfunction "S_1") (pintype "passive"))
      (node (ref "MENU") (pin "2") (pinfunction "S_2") (pintype "passive"))
      (node (ref "R11") (pin "2") (pinfunction "2_2") (pintype "passive"))
      (node (ref "U3") (pin "1") (pinfunction "A_1") (pintype "tri_state"))
    )
    (net (code "42") (name "Net-(U3B-A)") (class "Default")
      (node (ref "C5") (pin "1") (pinfunction "1_1") (pintype "passive"))
      (node (ref "R10") (pin "2") (pinfunction "2_2") (pintype "passive"))
      (node (ref "RIGHT") (pin "1") (pinfunction "S_1") (pintype "passive"))
      (node (ref "RIGHT") (pin "2") (pinfunction "S_2") (pintype "passive"))
      (node (ref "U3") (pin "4") (pinfunction "A_4") (pintype "tri_state"))
    )
    (net (code "43") (name "Net-(U3C-A)") (class "Default")
      (node (ref "C4") (pin "1") (pinfunction "1_1") (pintype "passive"))
      (node (ref "OK") (pin "1") (pinfunction "S_1") (pintype "passive"))
      (node (ref "OK") (pin "2") (pinfunction "S_2") (pintype "passive"))
      (node (ref "R9") (pin "2") (pinfunction "2_2") (pintype "passive"))
      (node (ref "U3") (pin "8") (pinfunction "A_8") (pintype "tri_state"))
    )
    (net (code "44") (name "Net-(U3D-A)") (class "Default")
      (node (ref "C3") (pin "1") (pinfunction "1_1") (pintype "passive"))
      (node (ref "LEFT") (pin "1") (pinfunction "S_1") (pintype "passive"))
      (node (ref "LEFT") (pin "2") (pinfunction "S_2") (pintype "passive"))
      (node (ref "R8") (pin "2") (pinfunction "2_2") (pintype "passive"))
      (node (ref "U3") (pin "11") (pinfunction "A_11") (pintype "tri_state"))
    )
    (net (code "45") (name "Net-(U8B-VOUT_A)") (class "Default")
      (node (ref "R42") (pin "1") (pinfunction "1_1") (pintype "passive"))
      (node (ref "U8B") (pin "8") (pinfunction "VOUT_A_8") (pintype "output"))
    )
    (net (code "46") (name "Net-(U8B-VOUT_B)") (class "Default")
      (node (ref "R31") (pin "1") (pinfunction "1_1") (pintype "passive"))
      (node (ref "U8B") (pin "5") (pinfunction "VOUT_B_5") (pintype "output"))
    )
    (net (code "47") (name "Net-(U10A-+IN)") (class "Default")
      (node (ref "R31") (pin "2") (pinfunction "2_2") (pintype "passive"))
      (node (ref "R32") (pin "1") (pinfunction "1_1") (pintype "passive"))
      (node (ref "R33") (pin "2") (pinfunction "2_2") (pintype "passive"))
      (node (ref "U10") (pin "3") (pinfunction "+IN_3") (pintype "input"))
    )
    (net (code "48") (name "Net-(U10A--IN)") (class "Default")
      (node (ref "R34") (pin "1") (pinfunction "1_1") (pintype "passive"))
      (node (ref "R35") (pin "2") (pinfunction "2_2") (pintype "passive"))
      (node (ref "R36") (pin "1") (pinfunction "1_1") (pintype "passive"))
      (node (ref "U10") (pin "2") (pinfunction "-IN_2") (pintype "input"))
    )
    (net (code "49") (name "Net-(U10A-OUT)") (class "Default")
      (node (ref "R36") (pin "2") (pinfunction "2_2") (pintype "passive"))
      (node (ref "R39") (pin "1") (pinfunction "1_1") (pintype "passive"))
      (node (ref "U10") (pin "1") (pinfunction "OUT_1") (pintype "output"))
    )
    (net (code "50") (name "Net-(U10B-+IN)") (class "Default")
      (node (ref "R42") (pin "2") (pinfunction "2_2") (pintype "passive"))
      (node (ref "R43") (pin "1") (pinfunction "1_1") (pintype "passive"))
      (node (ref "R44") (pin "2") (pinfunction "2_2") (pintype "passive"))
      (node (ref "U10") (pin "5") (pinfunction "+IN_5") (pintype "input"))
    )
    (net (code "51") (name "Net-(U10B--IN)") (class "Default")
      (node (ref "R45") (pin "1") (pinfunction "1_1") (pintype "passive"))
      (node (ref "R46") (pin "2") (pinfunction "2_2") (pintype "passive"))
      (node (ref "R47") (pin "1") (pinfunction "1_1") (pintype "passive"))
      (node (ref "U10") (pin "6") (pinfunction "-IN_6") (pintype "input"))
    )
    (net (code "52") (name "Net-(U10B-OUT)") (class "Default")
      (node (ref "R47") (pin "2") (pinfunction "2_2") (pintype "passive"))
      (node (ref "R50") (pin "1") (pinfunction "1_1") (pintype "passive"))
      (node (ref "U10") (pin "7") (pinfunction "OUT_7") (pintype "output"))
    )
    (net (code "53") (name "PA0") (class "Default")
      (node (ref "Q1") (pin "3") (pinfunction "S_3") (pintype "passive"))
      (node (ref "Q2") (pin "3") (pinfunction "S_3") (pintype "passive"))
      (node (ref "Q4") (pin "3") (pinfunction "S_3") (pintype "passive"))
      (node (ref "Q5") (pin "3") (pinfunction "S_3") (pintype "passive"))
      (node (ref "R30") (pin "2") (pinfunction "2_2") (pintype "passive"))
      (node (ref "R30_2") (pin "2") (pinfunction "2_2") (pintype "passive"))
      (node (ref "U1") (pin "37") (pinfunction "(ADC0)PA0_37") (pintype "bidirectional"))
    )
    (net (code "54") (name "PA1") (class "Default")
      (node (ref "MULTI") (pin "2") (pinfunction "S_2") (pintype "passive"))
      (node (ref "U1") (pin "36") (pinfunction "(ADC1)PA1_36") (pintype "bidirectional"))
    )
    (net (code "55") (name "PA4") (class "Default")
      (node (ref "LEVEL_A") (pin "2") (pinfunction "S_2") (pintype "passive"))
      (node (ref "U1") (pin "33") (pinfunction "(ADC4)PA4_33") (pintype "bidirectional"))
    )
    (net (code "56") (name "PA5") (class "Default")
      (node (ref "LEVEL_B") (pin "2") (pinfunction "S_2") (pintype "passive"))
      (node (ref "U1") (pin "32") (pinfunction "(ADC5)PA5_32") (pintype "bidirectional"))
    )
    (net (code "57") (name "PB0") (class "Default")
      (node (ref "R48") (pin "2") (pinfunction "2_2") (pintype "passive"))
      (node (ref "R49") (pin "1") (pinfunction "1_1") (pintype "passive"))
      (node (ref "U1") (pin "40") (pinfunction "(T0/XCK)PB0_40") (pintype "bidirectional"))
    )
    (net (code "58") (name "PB1") (class "Default")
      (node (ref "R51") (pin "2") (pinfunction "2_2") (pintype "passive"))
      (node (ref "R52") (pin "1") (pinfunction "1_1") (pintype "passive"))
      (node (ref "U1") (pin "41") (pinfunction "(T1)PB1_41") (pintype "bidirectional"))
    )
    (net (code "59") (name "PB2") (class "Default")
      (node (ref "R37") (pin "2") (pinfunction "2_2") (pintype "passive"))
      (node (ref "R38") (pin "1") (pinfunction "1_1") (pintype "passive"))
      (node (ref "U1") (pin "42") (pinfunction "(AIN0/INT2)PB2_42") (pintype "bidirectional"))
    )
    (net (code "60") (name "PB3") (class "Default")
      (node (ref "R40") (pin "2") (pinfunction "2_2") (pintype "passive"))
      (node (ref "R41") (pin "1") (pinfunction "1_1") (pintype "passive"))
      (node (ref "U1") (pin "43") (pinfunction "(AIN1/OC0)PB3_43") (pintype "bidirectional"))
    )
    (net (code "61") (name "PB5") (class "Default")
      (node (ref "ISP1") (pin "4") (pinfunction "MOSI_4") (pintype "output"))
      (node (ref "U1") (pin "1") (pinfunction "(MOSI)PB5_1") (pintype "bidirectional"))
      (node (ref "U8B") (pin "3") (pinfunction "D_IN_3") (pintype "input"))
    )
    (net (code "62") (name "PB6") (class "Default")
      (node (ref "ISP1") (pin "1") (pinfunction "MISO_1") (pintype "input"))
      (node (ref "U1") (pin "2") (pinfunction "(MISO)PB6_2") (pintype "bidirectional"))
    )
    (net (code "63") (name "PB7") (class "Default")
      (node (ref "ISP1") (pin "3") (pinfunction "SCK_3") (pintype "output"))
      (node (ref "U1") (pin "3") (pinfunction "(SCK)PB7_3") (pintype "bidirectional"))
      (node (ref "U8B") (pin "2") (pinfunction "SCK_2") (pintype "input"))
    )
    (net (code "64") (name "PC0") (class "Default")
      (node (ref "U1") (pin "19") (pinfunction "PC0(SCL)_19") (pintype "bidirectional"))
      (node (ref "U3") (pin "12") (pinfunction "C_12") (pintype "input"))
      (node (ref "U3") (pin "13") (pinfunction "C_13") (pintype "input"))
      (node (ref "U3") (pin "5") (pinfunction "C_5") (pintype "input"))
      (node (ref "U3") (pin "6") (pinfunction "C_6") (pintype "input"))
    )
    (net (code "65") (name "PC1") (class "Default")
      (node (ref "LCD1") (pin "5") (pinfunction "RW_5") (pintype "input"))
      (node (ref "U1") (pin "20") (pinfunction "PC1(SDA)_20") (pintype "bidirectional"))
    )
    (net (code "66") (name "PC2") (class "Default")
      (node (ref "LCD1") (pin "6") (pinfunction "E_6") (pintype "input"))
      (node (ref "U1") (pin "21") (pinfunction "(TCK)PC2_21") (pintype "bidirectional"))
    )
    (net (code "67") (name "PC3") (class "Default")
      (node (ref "LCD1") (pin "4") (pinfunction "RS_4") (pintype "input"))
      (node (ref "U1") (pin "22") (pinfunction "(TMS)PC3_22") (pintype "bidirectional"))
    )
    (net (code "68") (name "PC4") (class "Default")
      (node (ref "LCD1") (pin "11") (pinfunction "DB4_11") (pintype "bidirectional"))
      (node (ref "U1") (pin "23") (pinfunction "(TDO)PC4_23") (pintype "bidirectional"))
      (node (ref "U3") (pin "10") (pinfunction "B_10") (pintype "tri_state"))
    )
    (net (code "69") (name "PC5") (class "Default")
      (node (ref "LCD1") (pin "12") (pinfunction "DB5_12") (pintype "bidirectional"))
      (node (ref "U1") (pin "24") (pinfunction "(TDI)PC5_24") (pintype "bidirectional"))
      (node (ref "U3") (pin "9") (pinfunction "B_9") (pintype "tri_state"))
    )
    (net (code "70") (name "PC6") (class "Default")
      (node (ref "LCD1") (pin "13") (pinfunction "DB6_13") (pintype "bidirectional"))
      (node (ref "U1") (pin "25") (pinfunction "(TOSC1)PC6_25") (pintype "bidirectional"))
      (node (ref "U3") (pin "3") (pinfunction "B_3") (pintype "tri_state"))
    )
    (net (code "71") (name "PC7") (class "Default")
      (node (ref "LCD1") (pin "14") (pinfunction "DB7_14") (pintype "bidirectional"))
      (node (ref "U1") (pin "26") (pinfunction "(TOSC2)PC7_26") (pintype "bidirectional"))
      (node (ref "U3") (pin "2") (pinfunction "B_2") (pintype "tri_state"))
    )
    (net (code "72") (name "PD5") (class "Default")
      (node (ref "LED_CH_B") (pin "K") (pinfunction "C_K") (pintype "passive"))
      (node (ref "U1") (pin "14") (pinfunction "(OC1A)PD5_14") (pintype "bidirectional"))
    )
    (net (code "73") (name "PD6") (class "Default")
      (node (ref "LED_CH_A") (pin "K") (pinfunction "C_K") (pintype "passive"))
      (node (ref "U1") (pin "15") (pinfunction "(ICP)PD6_15") (pintype "bidirectional"))
    )
    (net (code "74") (name "PD7") (class "Default")
      (node (ref "R56") (pin "2") (pinfunction "2_2") (pintype "passive"))
      (node (ref "U1") (pin "16") (pinfunction "(OC2)PD7_16") (pintype "bidirectional"))
    )
    (net (code "75") (name "RESET") (class "Default")
      (node (ref "C8") (pin "1") (pinfunction "1_1") (pintype "passive"))
      (node (ref "ISP1") (pin "5") (pinfunction "RST_5") (pintype "output"))
      (node (ref "R3") (pin "1") (pinfunction "1_1") (pintype "passive"))
      (node (ref "U1") (pin "4") (pinfunction "RESET_4") (pintype "input"))
    )
    (net (code "76") (name "unconnected-(CHAN_A-Pad2)") (class "Default")
      (node (ref "CHAN_A") (pin "2") (pinfunction "2_2") (pintype "bidirectional"))
    )
    (net (code "77") (name "unconnected-(CHAN_B-Pad2)") (class "Default")
      (node (ref "CHAN_B") (pin "2") (pinfunction "2_2") (pintype "bidirectional"))
    )
    (net (code "78") (name "unconnected-(DC_IN-SLEEVE_SHUNT-Pad2)") (class "Default")
      (node (ref "DC_IN") (pin "2") (pinfunction "SLEEVE_SHUNT_2") (pintype "bidirectional"))
    )
    (net (code "79") (name "unconnected-(LCD1-DB0-Pad7)") (class "Default")
      (node (ref "LCD1") (pin "7") (pinfunction "DB0_7") (pintype "bidirectional"))
    )
    (net (code "80") (name "unconnected-(LCD1-DB1-Pad8)") (class "Default")
      (node (ref "LCD1") (pin "8") (pinfunction "DB1_8") (pintype "bidirectional"))
    )
    (net (code "81") (name "unconnected-(LCD1-DB2-Pad9)") (class "Default")
      (node (ref "LCD1") (pin "9") (pinfunction "DB2_9") (pintype "bidirectional"))
    )
    (net (code "82") (name "unconnected-(LCD1-DB3-Pad10)") (class "Default")
      (node (ref "LCD1") (pin "10") (pinfunction "DB3_10") (pintype "bidirectional"))
    )
    (net (code "83") (name "unconnected-(TR1-Pad2)") (class "Default")
      (node (ref "TR1") (pin "2") (pinfunction "2_2") (pintype "passive"))
    )
    (net (code "84") (name "unconnected-(TR2-Pad2)") (class "Default")
      (node (ref "TR2") (pin "2") (pinfunction "2_2") (pintype "passive"))
    )
    (net (code "85") (name "unconnected-(U$1-TRIM-Pad4)") (class "Default")
      (node (ref "U$1") (pin "4") (pinfunction "TRIM_4") (pintype "input"))
    )
    (net (code "86") (name "unconnected-(U1-(INT0)PD2-Pad11)") (class "Default")
      (node (ref "U1") (pin "11") (pinfunction "(INT0)PD2_11") (pintype "bidirectional"))
    )
    (net (code "87") (name "unconnected-(U1-(INT1)PD3-Pad12)") (class "Default")
      (node (ref "U1") (pin "12") (pinfunction "(INT1)PD3_12") (pintype "bidirectional"))
    )
    (net (code "88") (name "unconnected-(U1-(SS)PB4-Pad44)") (class "Default")
      (node (ref "U1") (pin "44") (pinfunction "(SS)PB4_44") (pintype "bidirectional"))
    )
    (net (code "89") (name "~{CS}") (class "Default")
      (node (ref "U1") (pin "13") (pinfunction "(OC1B)PD4_13") (pintype "bidirectional"))
      (node (ref "U8B") (pin "1") (pinfunction "CS/LD_1") (pintype "input"))
    )
  )
)
